# FT323H_IF.net
KiCad netlist of a schematic drawn in EAGLE
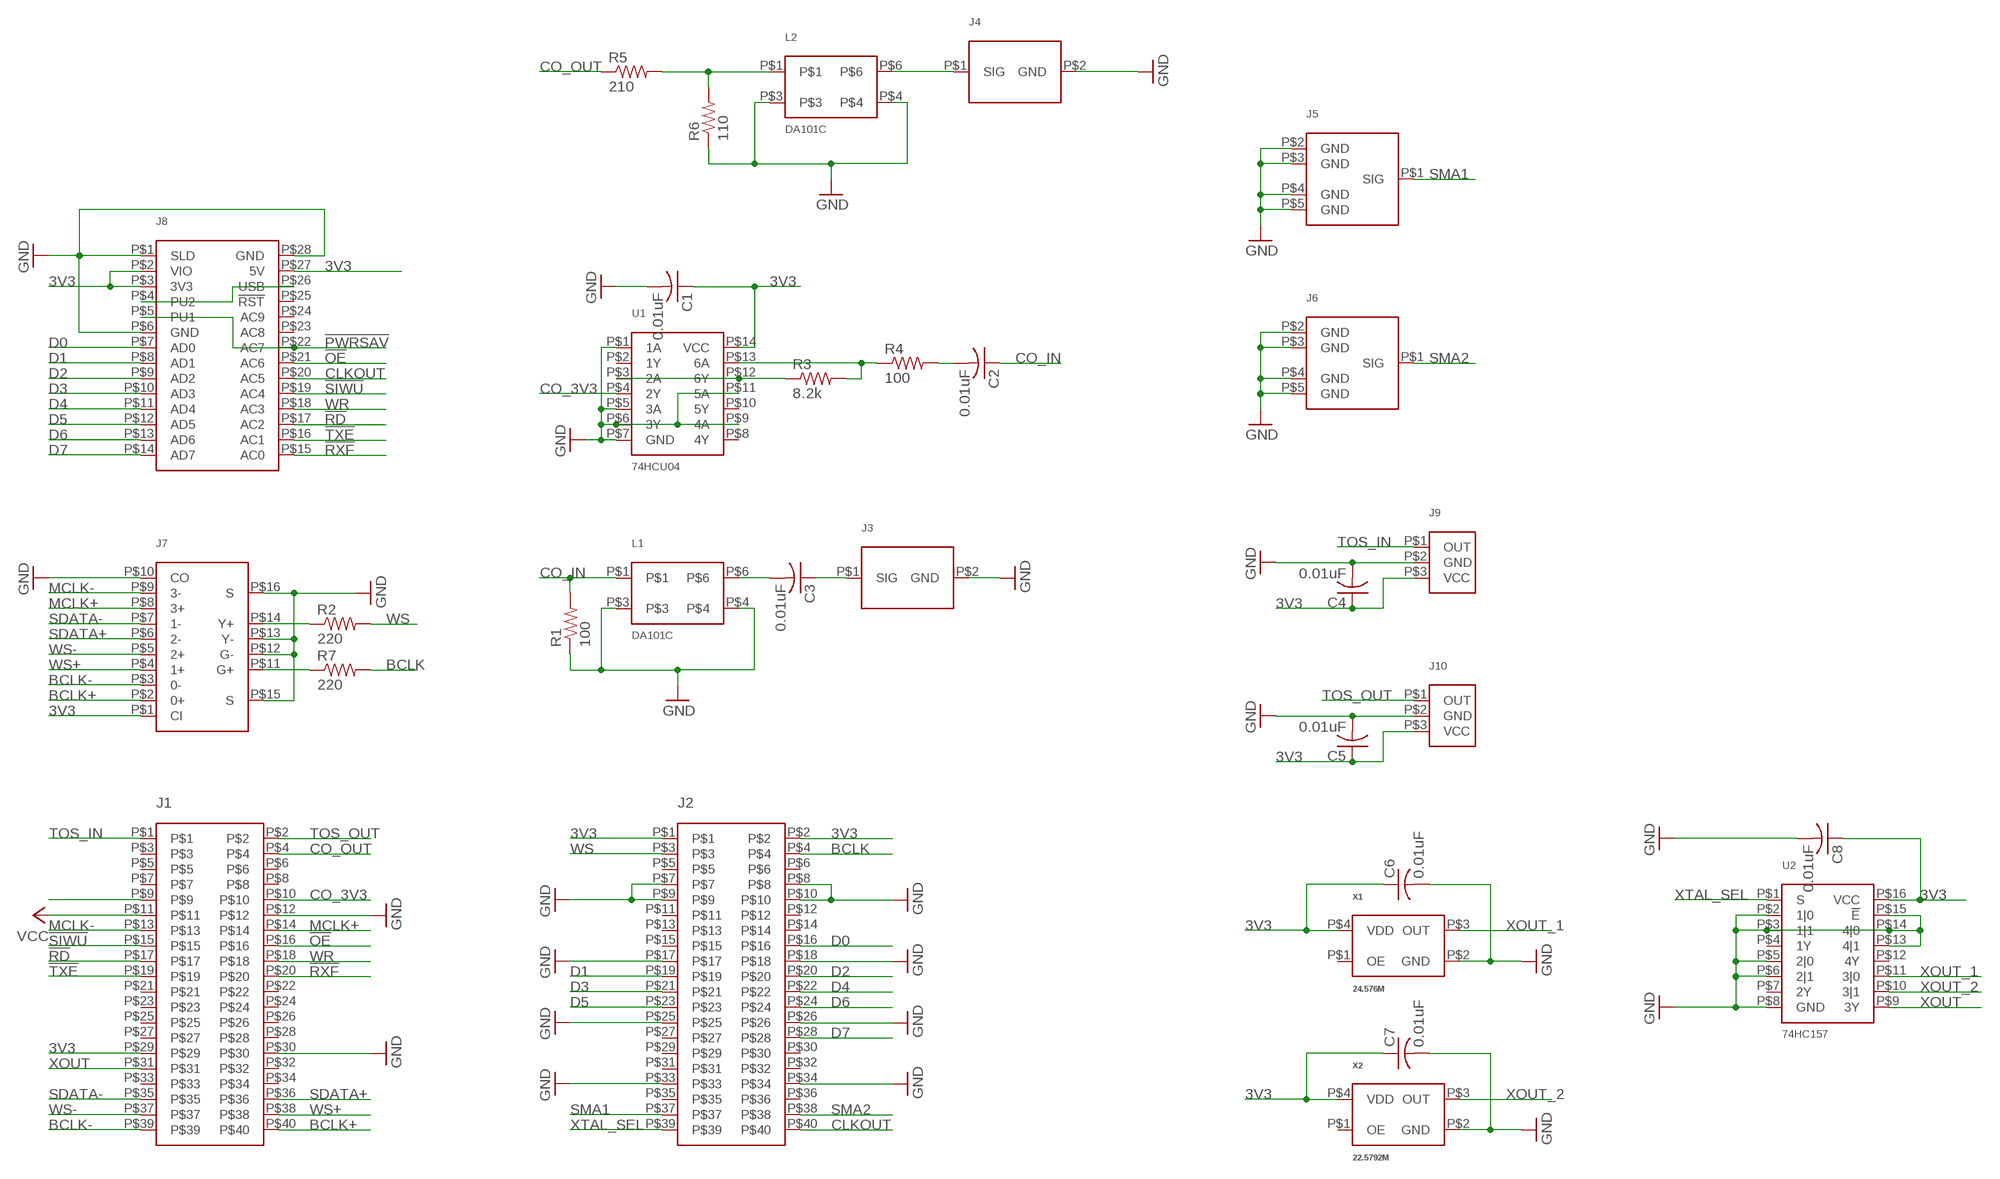
[diagram p0: schematic, sheet 1]

(export (version "E")
  (design (tool "Eeschema 10.0.6"))
  (components
    (comp (ref "C1")
      (value "0.01uF")
      (footprint "eagle-import:C0805")
      (libsource (lib "eagle-import") (part "C-USC0805"))
    )
    (comp (ref "C2")
      (value "0.01uF")
      (footprint "eagle-import:MKS2")
      (libsource (lib "eagle-import") (part "MKS2"))
    )
    (comp (ref "C3")
      (value "0.01uF")
      (footprint "eagle-import:MKS2")
      (libsource (lib "eagle-import") (part "MKS2"))
    )
    (comp (ref "C4")
      (value "0.01uF")
      (footprint "eagle-import:C0805")
      (libsource (lib "eagle-import") (part "C-USC0805"))
    )
    (comp (ref "C5")
      (value "0.01uF")
      (footprint "eagle-import:C0805")
      (libsource (lib "eagle-import") (part "C-USC0805"))
    )
    (comp (ref "C6")
      (value "0.01uF")
      (footprint "eagle-import:C0805")
      (libsource (lib "eagle-import") (part "C-USC0805"))
    )
    (comp (ref "C7")
      (value "0.01uF")
      (footprint "eagle-import:C0805")
      (libsource (lib "eagle-import") (part "C-USC0805"))
    )
    (comp (ref "C8")
      (value "0.01uF")
      (footprint "eagle-import:C0805")
      (libsource (lib "eagle-import") (part "C-USC0805"))
    )
    (comp (ref "J1")
      (value "JUMPER-2X20")
      (footprint "eagle-import:JUMPER-2X20-2.54MM")
      (libsource (lib "eagle-import") (part "JUMPER-2X20"))
    )
    (comp (ref "J2")
      (value "JUMPER-2X20")
      (footprint "eagle-import:JUMPER-2X20-2.54MM")
      (libsource (lib "eagle-import") (part "JUMPER-2X20"))
    )
    (comp (ref "J3")
      (value "RCA")
      (footprint "eagle-import:RCA")
      (libsource (lib "eagle-import") (part "RCA"))
    )
    (comp (ref "J4")
      (value "RCA")
      (footprint "eagle-import:RCA")
      (libsource (lib "eagle-import") (part "RCA"))
    )
    (comp (ref "J5")
      (value "SMA")
      (footprint "eagle-import:SMA")
      (libsource (lib "eagle-import") (part "SMA"))
    )
    (comp (ref "J6")
      (value "SMA")
      (footprint "eagle-import:SMA")
      (libsource (lib "eagle-import") (part "SMA"))
    )
    (comp (ref "J7")
      (value "HR911130C")
      (footprint "eagle-import:HR911130C")
      (libsource (lib "eagle-import") (part "HR911130C"))
    )
    (comp (ref "J8")
      (value "UM232H")
      (footprint "eagle-import:UM232H")
      (libsource (lib "eagle-import") (part "UM232H"))
    )
    (comp (ref "J9")
      (value "TORX178A")
      (footprint "eagle-import:TORX178A")
      (libsource (lib "eagle-import") (part "TORX178A"))
    )
    (comp (ref "J10")
      (value "TORX178A")
      (footprint "eagle-import:TORX178A")
      (libsource (lib "eagle-import") (part "TORX178A"))
    )
    (comp (ref "L1")
      (value "DA101C")
      (footprint "eagle-import:DA101C")
      (libsource (lib "eagle-import") (part "DA101C"))
    )
    (comp (ref "L2")
      (value "DA101C")
      (footprint "eagle-import:DA101C")
      (libsource (lib "eagle-import") (part "DA101C"))
    )
    (comp (ref "R1")
      (value "100")
      (footprint "eagle-import:RJ-24")
      (libsource (lib "eagle-import") (part "RES-RJ24"))
    )
    (comp (ref "R2")
      (value "220")
      (footprint "eagle-import:RJ-24")
      (libsource (lib "eagle-import") (part "RES-RJ24"))
    )
    (comp (ref "R3")
      (value "8.2k")
      (footprint "eagle-import:RJ-24")
      (libsource (lib "eagle-import") (part "RES-RJ24"))
    )
    (comp (ref "R4")
      (value "100")
      (footprint "eagle-import:RJ-24")
      (libsource (lib "eagle-import") (part "RES-RJ24"))
    )
    (comp (ref "R5")
      (value "210")
      (footprint "eagle-import:RJ-24")
      (libsource (lib "eagle-import") (part "RES-RJ24"))
    )
    (comp (ref "R6")
      (value "110")
      (footprint "eagle-import:RJ-24")
      (libsource (lib "eagle-import") (part "RES-RJ24"))
    )
    (comp (ref "R7")
      (value "220")
      (footprint "eagle-import:RJ-24")
      (libsource (lib "eagle-import") (part "RES-RJ24"))
    )
    (comp (ref "U1")
      (value "74HCU04")
      (footprint "eagle-import:74HCU04D")
      (libsource (lib "eagle-import") (part "74HCU04"))
    )
    (comp (ref "U2")
      (value "74HC157")
      (footprint "eagle-import:74HC157D-SO16")
      (libsource (lib "eagle-import") (part "74HC157"))
    )
    (comp (ref "X1")
      (value "24.576M")
      (footprint "eagle-import:SIT8208-0507")
      (libsource (lib "eagle-import") (part "SIT8208"))
    )
    (comp (ref "X2")
      (value "22.5792M")
      (footprint "eagle-import:SIT8208-0507")
      (libsource (lib "eagle-import") (part "SIT8208"))
    )
  )
  (nets
    (net (code "1") (name "/3V3") (class "Default")
      (node (ref "C1") (pin "1") (pinfunction "1_1") (pintype "passive"))
      (node (ref "C4") (pin "1") (pinfunction "1_1") (pintype "passive"))
      (node (ref "C5") (pin "1") (pinfunction "1_1") (pintype "passive"))
      (node (ref "C6") (pin "1") (pinfunction "1_1") (pintype "passive"))
      (node (ref "C7") (pin "1") (pinfunction "1_1") (pintype "passive"))
      (node (ref "C8") (pin "1") (pinfunction "1_1") (pintype "passive"))
      (node (ref "J1") (pin "P$29") (pinfunction "P$29_P$29") (pintype "bidirectional"))
      (node (ref "J10") (pin "P$3") (pinfunction "VCC_P$3") (pintype "bidirectional"))
      (node (ref "J2") (pin "P$1") (pinfunction "P$1_P$1") (pintype "bidirectional"))
      (node (ref "J2") (pin "P$2") (pinfunction "P$2_P$2") (pintype "bidirectional"))
      (node (ref "J7") (pin "P$1") (pinfunction "CI_P$1") (pintype "bidirectional"))
      (node (ref "J8") (pin "P$2") (pinfunction "VIO_P$2") (pintype "bidirectional"))
      (node (ref "J8") (pin "P$27") (pinfunction "5V_P$27") (pintype "bidirectional"))
      (node (ref "J8") (pin "P$3") (pinfunction "3V3_P$3") (pintype "bidirectional"))
      (node (ref "J9") (pin "P$3") (pinfunction "VCC_P$3") (pintype "bidirectional"))
      (node (ref "U1") (pin "P$14") (pinfunction "VCC_P$14") (pintype "bidirectional"))
      (node (ref "U2") (pin "P$16") (pinfunction "VCC_P$16") (pintype "bidirectional"))
      (node (ref "X1") (pin "P$4") (pinfunction "VDD_P$4") (pintype "bidirectional"))
      (node (ref "X2") (pin "P$4") (pinfunction "VDD_P$4") (pintype "bidirectional"))
    )
    (net (code "2") (name "/BCLK") (class "Default")
      (node (ref "J2") (pin "P$4") (pinfunction "P$4_P$4") (pintype "bidirectional"))
      (node (ref "R7") (pin "P$2") (pinfunction "2_P$2") (pintype "passive"))
    )
    (net (code "3") (name "/BCLK+") (class "Default")
      (node (ref "J1") (pin "P$40") (pinfunction "P$40_P$40") (pintype "bidirectional"))
      (node (ref "J7") (pin "P$2") (pinfunction "0+_P$2") (pintype "bidirectional"))
    )
    (net (code "4") (name "/BCLK-") (class "Default")
      (node (ref "J1") (pin "P$39") (pinfunction "P$39_P$39") (pintype "bidirectional"))
      (node (ref "J7") (pin "P$3") (pinfunction "0-_P$3") (pintype "bidirectional"))
    )
    (net (code "5") (name "/CLKOUT") (class "Default")
      (node (ref "J2") (pin "P$40") (pinfunction "P$40_P$40") (pintype "bidirectional"))
      (node (ref "J8") (pin "P$20") (pinfunction "AC5_P$20") (pintype "bidirectional"))
    )
    (net (code "6") (name "/CO_3V3") (class "Default")
      (node (ref "J1") (pin "P$10") (pinfunction "P$10_P$10") (pintype "bidirectional"))
      (node (ref "U1") (pin "P$4") (pinfunction "2Y_P$4") (pintype "bidirectional"))
    )
    (net (code "7") (name "/CO_IN") (class "Default")
      (node (ref "C2") (pin "P$1") (pinfunction "1_P$1") (pintype "passive"))
      (node (ref "L1") (pin "P$1") (pinfunction "P$1_P$1") (pintype "bidirectional"))
      (node (ref "R1") (pin "P$2") (pinfunction "2_P$2") (pintype "passive"))
    )
    (net (code "8") (name "/CO_OUT") (class "Default")
      (node (ref "J1") (pin "P$4") (pinfunction "P$4_P$4") (pintype "bidirectional"))
      (node (ref "R5") (pin "P$1") (pinfunction "1_P$1") (pintype "passive"))
    )
    (net (code "9") (name "/D0") (class "Default")
      (node (ref "J2") (pin "P$16") (pinfunction "P$16_P$16") (pintype "bidirectional"))
      (node (ref "J8") (pin "P$7") (pinfunction "AD0_P$7") (pintype "bidirectional"))
    )
    (net (code "10") (name "/D1") (class "Default")
      (node (ref "J2") (pin "P$19") (pinfunction "P$19_P$19") (pintype "bidirectional"))
      (node (ref "J8") (pin "P$8") (pinfunction "AD1_P$8") (pintype "bidirectional"))
    )
    (net (code "11") (name "/D2") (class "Default")
      (node (ref "J2") (pin "P$20") (pinfunction "P$20_P$20") (pintype "bidirectional"))
      (node (ref "J8") (pin "P$9") (pinfunction "AD2_P$9") (pintype "bidirectional"))
    )
    (net (code "12") (name "/D3") (class "Default")
      (node (ref "J2") (pin "P$21") (pinfunction "P$21_P$21") (pintype "bidirectional"))
      (node (ref "J8") (pin "P$10") (pinfunction "AD3_P$10") (pintype "bidirectional"))
    )
    (net (code "13") (name "/D4") (class "Default")
      (node (ref "J2") (pin "P$22") (pinfunction "P$22_P$22") (pintype "bidirectional"))
      (node (ref "J8") (pin "P$11") (pinfunction "AD4_P$11") (pintype "bidirectional"))
    )
    (net (code "14") (name "/D5") (class "Default")
      (node (ref "J2") (pin "P$23") (pinfunction "P$23_P$23") (pintype "bidirectional"))
      (node (ref "J8") (pin "P$12") (pinfunction "AD5_P$12") (pintype "bidirectional"))
    )
    (net (code "15") (name "/D6") (class "Default")
      (node (ref "J2") (pin "P$24") (pinfunction "P$24_P$24") (pintype "bidirectional"))
      (node (ref "J8") (pin "P$13") (pinfunction "AD6_P$13") (pintype "bidirectional"))
    )
    (net (code "16") (name "/D7") (class "Default")
      (node (ref "J2") (pin "P$28") (pinfunction "P$28_P$28") (pintype "bidirectional"))
      (node (ref "J8") (pin "P$14") (pinfunction "AD7_P$14") (pintype "bidirectional"))
    )
    (net (code "17") (name "/MCLK+") (class "Default")
      (node (ref "J1") (pin "P$14") (pinfunction "P$14_P$14") (pintype "bidirectional"))
      (node (ref "J7") (pin "P$8") (pinfunction "3+_P$8") (pintype "bidirectional"))
    )
    (net (code "18") (name "/MCLK-") (class "Default")
      (node (ref "J1") (pin "P$13") (pinfunction "P$13_P$13") (pintype "bidirectional"))
      (node (ref "J7") (pin "P$9") (pinfunction "3-_P$9") (pintype "bidirectional"))
    )
    (net (code "19") (name "/SDATA+") (class "Default")
      (node (ref "J1") (pin "P$36") (pinfunction "P$36_P$36") (pintype "bidirectional"))
      (node (ref "J7") (pin "P$6") (pinfunction "2-_P$6") (pintype "bidirectional"))
    )
    (net (code "20") (name "/SDATA-") (class "Default")
      (node (ref "J1") (pin "P$35") (pinfunction "P$35_P$35") (pintype "bidirectional"))
      (node (ref "J7") (pin "P$7") (pinfunction "1-_P$7") (pintype "bidirectional"))
    )
    (net (code "21") (name "/SMA1") (class "Default")
      (node (ref "J2") (pin "P$37") (pinfunction "P$37_P$37") (pintype "bidirectional"))
      (node (ref "J5") (pin "P$1") (pinfunction "SIG_P$1") (pintype "bidirectional"))
    )
    (net (code "22") (name "/SMA2") (class "Default")
      (node (ref "J2") (pin "P$38") (pinfunction "P$38_P$38") (pintype "bidirectional"))
      (node (ref "J6") (pin "P$1") (pinfunction "SIG_P$1") (pintype "bidirectional"))
    )
    (net (code "23") (name "/TOS_IN") (class "Default")
      (node (ref "J1") (pin "P$1") (pinfunction "P$1_P$1") (pintype "bidirectional"))
      (node (ref "J9") (pin "P$1") (pinfunction "OUT_P$1") (pintype "bidirectional"))
    )
    (net (code "24") (name "/TOS_OUT") (class "Default")
      (node (ref "J1") (pin "P$2") (pinfunction "P$2_P$2") (pintype "bidirectional"))
      (node (ref "J10") (pin "P$1") (pinfunction "OUT_P$1") (pintype "bidirectional"))
    )
    (net (code "25") (name "/WR") (class "Default")
      (node (ref "J1") (pin "P$18") (pinfunction "P$18_P$18") (pintype "bidirectional"))
      (node (ref "J8") (pin "P$18") (pinfunction "AC3_P$18") (pintype "bidirectional"))
    )
    (net (code "26") (name "/WS") (class "Default")
      (node (ref "J2") (pin "P$3") (pinfunction "P$3_P$3") (pintype "bidirectional"))
      (node (ref "R2") (pin "P$2") (pinfunction "2_P$2") (pintype "passive"))
    )
    (net (code "27") (name "/WS+") (class "Default")
      (node (ref "J1") (pin "P$38") (pinfunction "P$38_P$38") (pintype "bidirectional"))
      (node (ref "J7") (pin "P$4") (pinfunction "1+_P$4") (pintype "bidirectional"))
    )
    (net (code "28") (name "/WS-") (class "Default")
      (node (ref "J1") (pin "P$37") (pinfunction "P$37_P$37") (pintype "bidirectional"))
      (node (ref "J7") (pin "P$5") (pinfunction "2+_P$5") (pintype "bidirectional"))
    )
    (net (code "29") (name "/XOUT") (class "Default")
      (node (ref "J1") (pin "P$31") (pinfunction "P$31_P$31") (pintype "bidirectional"))
      (node (ref "U2") (pin "P$9") (pinfunction "3Y_P$9") (pintype "bidirectional"))
    )
    (net (code "30") (name "/XOUT_1") (class "Default")
      (node (ref "U2") (pin "P$11") (pinfunction "3|0_P$11") (pintype "bidirectional"))
      (node (ref "X1") (pin "P$3") (pinfunction "OUT_P$3") (pintype "bidirectional"))
    )
    (net (code "31") (name "/XOUT_2") (class "Default")
      (node (ref "U2") (pin "P$10") (pinfunction "3|1_P$10") (pintype "bidirectional"))
      (node (ref "X2") (pin "P$3") (pinfunction "OUT_P$3") (pintype "bidirectional"))
    )
    (net (code "32") (name "/XTAL_SEL") (class "Default")
      (node (ref "J2") (pin "P$39") (pinfunction "P$39_P$39") (pintype "bidirectional"))
      (node (ref "U2") (pin "P$1") (pinfunction "S_P$1") (pintype "bidirectional"))
    )
    (net (code "33") (name "/~{OE}") (class "Default")
      (node (ref "J1") (pin "P$16") (pinfunction "P$16_P$16") (pintype "bidirectional"))
      (node (ref "J8") (pin "P$21") (pinfunction "AC6_P$21") (pintype "bidirectional"))
    )
    (net (code "34") (name "/~{PWRSAV}") (class "Default")
      (node (ref "J8") (pin "P$22") (pinfunction "AC7_P$22") (pintype "bidirectional"))
      (node (ref "J8") (pin "P$5") (pinfunction "PU1_P$5") (pintype "bidirectional"))
    )
    (net (code "35") (name "/~{RD}") (class "Default")
      (node (ref "J1") (pin "P$17") (pinfunction "P$17_P$17") (pintype "bidirectional"))
      (node (ref "J8") (pin "P$17") (pinfunction "AC2_P$17") (pintype "bidirectional"))
    )
    (net (code "36") (name "/~{RXF}") (class "Default")
      (node (ref "J1") (pin "P$20") (pinfunction "P$20_P$20") (pintype "bidirectional"))
      (node (ref "J8") (pin "P$15") (pinfunction "AC0_P$15") (pintype "bidirectional"))
    )
    (net (code "37") (name "/~{SIWU}") (class "Default")
      (node (ref "J1") (pin "P$15") (pinfunction "P$15_P$15") (pintype "bidirectional"))
      (node (ref "J8") (pin "P$19") (pinfunction "AC4_P$19") (pintype "bidirectional"))
    )
    (net (code "38") (name "/~{TXE}") (class "Default")
      (node (ref "J1") (pin "P$19") (pinfunction "P$19_P$19") (pintype "bidirectional"))
      (node (ref "J8") (pin "P$16") (pinfunction "AC1_P$16") (pintype "bidirectional"))
    )
    (net (code "39") (name "GND") (class "Default")
      (node (ref "C1") (pin "2") (pinfunction "2_2") (pintype "passive"))
      (node (ref "C4") (pin "2") (pinfunction "2_2") (pintype "passive"))
      (node (ref "C5") (pin "2") (pinfunction "2_2") (pintype "passive"))
      (node (ref "C6") (pin "2") (pinfunction "2_2") (pintype "passive"))
      (node (ref "C7") (pin "2") (pinfunction "2_2") (pintype "passive"))
      (node (ref "C8") (pin "2") (pinfunction "2_2") (pintype "passive"))
      (node (ref "J1") (pin "P$12") (pinfunction "P$12_P$12") (pintype "bidirectional"))
      (node (ref "J1") (pin "P$30") (pinfunction "P$30_P$30") (pintype "bidirectional"))
      (node (ref "J10") (pin "P$2") (pinfunction "GND_P$2") (pintype "bidirectional"))
      (node (ref "J2") (pin "P$10") (pinfunction "P$10_P$10") (pintype "bidirectional"))
      (node (ref "J2") (pin "P$17") (pinfunction "P$17_P$17") (pintype "bidirectional"))
      (node (ref "J2") (pin "P$18") (pinfunction "P$18_P$18") (pintype "bidirectional"))
      (node (ref "J2") (pin "P$25") (pinfunction "P$25_P$25") (pintype "bidirectional"))
      (node (ref "J2") (pin "P$26") (pinfunction "P$26_P$26") (pintype "bidirectional"))
      (node (ref "J2") (pin "P$33") (pinfunction "P$33_P$33") (pintype "bidirectional"))
      (node (ref "J2") (pin "P$34") (pinfunction "P$34_P$34") (pintype "bidirectional"))
      (node (ref "J2") (pin "P$7") (pinfunction "P$7_P$7") (pintype "bidirectional"))
      (node (ref "J2") (pin "P$8") (pinfunction "P$8_P$8") (pintype "bidirectional"))
      (node (ref "J2") (pin "P$9") (pinfunction "P$9_P$9") (pintype "bidirectional"))
      (node (ref "J3") (pin "P$2") (pinfunction "GND_P$2") (pintype "bidirectional"))
      (node (ref "J4") (pin "P$2") (pinfunction "GND_P$2") (pintype "bidirectional"))
      (node (ref "J5") (pin "P$2") (pinfunction "GND_P$2") (pintype "bidirectional"))
      (node (ref "J5") (pin "P$3") (pinfunction "GND_P$3") (pintype "bidirectional"))
      (node (ref "J5") (pin "P$4") (pinfunction "GND_P$4") (pintype "bidirectional"))
      (node (ref "J5") (pin "P$5") (pinfunction "GND_P$5") (pintype "bidirectional"))
      (node (ref "J6") (pin "P$2") (pinfunction "GND_P$2") (pintype "bidirectional"))
      (node (ref "J6") (pin "P$3") (pinfunction "GND_P$3") (pintype "bidirectional"))
      (node (ref "J6") (pin "P$4") (pinfunction "GND_P$4") (pintype "bidirectional"))
      (node (ref "J6") (pin "P$5") (pinfunction "GND_P$5") (pintype "bidirectional"))
      (node (ref "J7") (pin "P$10") (pinfunction "CO_P$10") (pintype "bidirectional"))
      (node (ref "J7") (pin "P$12") (pinfunction "G-_P$12") (pintype "bidirectional"))
      (node (ref "J7") (pin "P$13") (pinfunction "Y-_P$13") (pintype "bidirectional"))
      (node (ref "J7") (pin "P$15") (pinfunction "S_P$15") (pintype "bidirectional"))
      (node (ref "J7") (pin "P$16") (pinfunction "S_P$16") (pintype "bidirectional"))
      (node (ref "J8") (pin "P$1") (pinfunction "SLD_P$1") (pintype "bidirectional"))
      (node (ref "J8") (pin "P$28") (pinfunction "GND_P$28") (pintype "bidirectional"))
      (node (ref "J8") (pin "P$6") (pinfunction "GND_P$6") (pintype "bidirectional"))
      (node (ref "J9") (pin "P$2") (pinfunction "GND_P$2") (pintype "bidirectional"))
      (node (ref "L1") (pin "P$3") (pinfunction "P$3_P$3") (pintype "bidirectional"))
      (node (ref "L1") (pin "P$4") (pinfunction "P$4_P$4") (pintype "bidirectional"))
      (node (ref "L2") (pin "P$3") (pinfunction "P$3_P$3") (pintype "bidirectional"))
      (node (ref "L2") (pin "P$4") (pinfunction "P$4_P$4") (pintype "bidirectional"))
      (node (ref "R1") (pin "P$1") (pinfunction "1_P$1") (pintype "passive"))
      (node (ref "R6") (pin "P$1") (pinfunction "1_P$1") (pintype "passive"))
      (node (ref "U1") (pin "P$1") (pinfunction "1A_P$1") (pintype "bidirectional"))
      (node (ref "U1") (pin "P$11") (pinfunction "5A_P$11") (pintype "bidirectional"))
      (node (ref "U1") (pin "P$5") (pinfunction "3A_P$5") (pintype "bidirectional"))
      (node (ref "U1") (pin "P$6") (pinfunction "3Y_P$6") (pintype "bidirectional"))
      (node (ref "U1") (pin "P$7") (pinfunction "GND_P$7") (pintype "bidirectional"))
      (node (ref "U1") (pin "P$9") (pinfunction "4A_P$9") (pintype "bidirectional"))
      (node (ref "U2") (pin "P$13") (pinfunction "4|1_P$13") (pintype "bidirectional"))
      (node (ref "U2") (pin "P$14") (pinfunction "4|0_P$14") (pintype "bidirectional"))
      (node (ref "U2") (pin "P$15") (pinfunction "~{E}_P$15") (pintype "bidirectional"))
      (node (ref "U2") (pin "P$2") (pinfunction "1|0_P$2") (pintype "bidirectional"))
      (node (ref "U2") (pin "P$3") (pinfunction "1|1_P$3") (pintype "bidirectional"))
      (node (ref "U2") (pin "P$5") (pinfunction "2|0_P$5") (pintype "bidirectional"))
      (node (ref "U2") (pin "P$6") (pinfunction "2|1_P$6") (pintype "bidirectional"))
      (node (ref "U2") (pin "P$8") (pinfunction "GND_P$8") (pintype "bidirectional"))
      (node (ref "X1") (pin "P$2") (pinfunction "GND_P$2") (pintype "bidirectional"))
      (node (ref "X2") (pin "P$2") (pinfunction "GND_P$2") (pintype "bidirectional"))
    )
    (net (code "40") (name "Net-(C2-2)") (class "Default")
      (node (ref "C2") (pin "P$2") (pinfunction "2_P$2") (pintype "passive"))
      (node (ref "R4") (pin "P$2") (pinfunction "2_P$2") (pintype "passive"))
    )
    (net (code "41") (name "Net-(C3-1)") (class "Default")
      (node (ref "C3") (pin "P$1") (pinfunction "1_P$1") (pintype "passive"))
      (node (ref "J3") (pin "P$1") (pinfunction "SIG_P$1") (pintype "bidirectional"))
    )
    (net (code "42") (name "Net-(C3-2)") (class "Default")
      (node (ref "C3") (pin "P$2") (pinfunction "2_P$2") (pintype "passive"))
      (node (ref "L1") (pin "P$6") (pinfunction "P$6_P$6") (pintype "bidirectional"))
    )
    (net (code "43") (name "Net-(J4-SIG)") (class "Default")
      (node (ref "J4") (pin "P$1") (pinfunction "SIG_P$1") (pintype "bidirectional"))
      (node (ref "L2") (pin "P$6") (pinfunction "P$6_P$6") (pintype "bidirectional"))
    )
    (net (code "44") (name "Net-(J7-G+)") (class "Default")
      (node (ref "J7") (pin "P$11") (pinfunction "G+_P$11") (pintype "bidirectional"))
      (node (ref "R7") (pin "P$1") (pinfunction "1_P$1") (pintype "passive"))
    )
    (net (code "45") (name "Net-(J7-Y+)") (class "Default")
      (node (ref "J7") (pin "P$14") (pinfunction "Y+_P$14") (pintype "bidirectional"))
      (node (ref "R2") (pin "P$1") (pinfunction "1_P$1") (pintype "passive"))
    )
    (net (code "46") (name "Net-(J8-PU2)") (class "Default")
      (node (ref "J8") (pin "P$26") (pinfunction "USB_P$26") (pintype "bidirectional"))
      (node (ref "J8") (pin "P$4") (pinfunction "PU2_P$4") (pintype "bidirectional"))
    )
    (net (code "47") (name "Net-(R3-1)") (class "Default")
      (node (ref "R3") (pin "P$1") (pinfunction "1_P$1") (pintype "passive"))
      (node (ref "U1") (pin "P$12") (pinfunction "6Y_P$12") (pintype "bidirectional"))
      (node (ref "U1") (pin "P$3") (pinfunction "2A_P$3") (pintype "bidirectional"))
    )
    (net (code "48") (name "Net-(R3-2)") (class "Default")
      (node (ref "R3") (pin "P$2") (pinfunction "2_P$2") (pintype "passive"))
      (node (ref "R4") (pin "P$1") (pinfunction "1_P$1") (pintype "passive"))
      (node (ref "U1") (pin "P$13") (pinfunction "6A_P$13") (pintype "bidirectional"))
    )
    (net (code "49") (name "Net-(R5-2)") (class "Default")
      (node (ref "L2") (pin "P$1") (pinfunction "P$1_P$1") (pintype "bidirectional"))
      (node (ref "R5") (pin "P$2") (pinfunction "2_P$2") (pintype "passive"))
      (node (ref "R6") (pin "P$2") (pinfunction "2_P$2") (pintype "passive"))
    )
    (net (code "50") (name "VCC") (class "Default")
      (node (ref "J1") (pin "P$11") (pinfunction "P$11_P$11") (pintype "bidirectional"))
    )
    (net (code "51") (name "unconnected-(J1-PadP$3)") (class "Default")
      (node (ref "J1") (pin "P$3") (pinfunction "P$3_P$3") (pintype "bidirectional"))
    )
    (net (code "52") (name "unconnected-(J1-PadP$5)") (class "Default")
      (node (ref "J1") (pin "P$5") (pinfunction "P$5_P$5") (pintype "bidirectional"))
    )
    (net (code "53") (name "unconnected-(J1-PadP$6)") (class "Default")
      (node (ref "J1") (pin "P$6") (pinfunction "P$6_P$6") (pintype "bidirectional"))
    )
    (net (code "54") (name "unconnected-(J1-PadP$7)") (class "Default")
      (node (ref "J1") (pin "P$7") (pinfunction "P$7_P$7") (pintype "bidirectional"))
    )
    (net (code "55") (name "unconnected-(J1-PadP$8)") (class "Default")
      (node (ref "J1") (pin "P$8") (pinfunction "P$8_P$8") (pintype "bidirectional"))
    )
    (net (code "56") (name "unconnected-(J1-PadP$9)") (class "Default")
      (node (ref "J1") (pin "P$9") (pinfunction "P$9_P$9") (pintype "bidirectional"))
    )
    (net (code "57") (name "unconnected-(J1-PadP$21)") (class "Default")
      (node (ref "J1") (pin "P$21") (pinfunction "P$21_P$21") (pintype "bidirectional"))
    )
    (net (code "58") (name "unconnected-(J1-PadP$22)") (class "Default")
      (node (ref "J1") (pin "P$22") (pinfunction "P$22_P$22") (pintype "bidirectional"))
    )
    (net (code "59") (name "unconnected-(J1-PadP$23)") (class "Default")
      (node (ref "J1") (pin "P$23") (pinfunction "P$23_P$23") (pintype "bidirectional"))
    )
    (net (code "60") (name "unconnected-(J1-PadP$24)") (class "Default")
      (node (ref "J1") (pin "P$24") (pinfunction "P$24_P$24") (pintype "bidirectional"))
    )
    (net (code "61") (name "unconnected-(J1-PadP$25)") (class "Default")
      (node (ref "J1") (pin "P$25") (pinfunction "P$25_P$25") (pintype "bidirectional"))
    )
    (net (code "62") (name "unconnected-(J1-PadP$26)") (class "Default")
      (node (ref "J1") (pin "P$26") (pinfunction "P$26_P$26") (pintype "bidirectional"))
    )
    (net (code "63") (name "unconnected-(J1-PadP$27)") (class "Default")
      (node (ref "J1") (pin "P$27") (pinfunction "P$27_P$27") (pintype "bidirectional"))
    )
    (net (code "64") (name "unconnected-(J1-PadP$28)") (class "Default")
      (node (ref "J1") (pin "P$28") (pinfunction "P$28_P$28") (pintype "bidirectional"))
    )
    (net (code "65") (name "unconnected-(J1-PadP$32)") (class "Default")
      (node (ref "J1") (pin "P$32") (pinfunction "P$32_P$32") (pintype "bidirectional"))
    )
    (net (code "66") (name "unconnected-(J1-PadP$33)") (class "Default")
      (node (ref "J1") (pin "P$33") (pinfunction "P$33_P$33") (pintype "bidirectional"))
    )
    (net (code "67") (name "unconnected-(J1-PadP$34)") (class "Default")
      (node (ref "J1") (pin "P$34") (pinfunction "P$34_P$34") (pintype "bidirectional"))
    )
    (net (code "68") (name "unconnected-(J2-PadP$5)") (class "Default")
      (node (ref "J2") (pin "P$5") (pinfunction "P$5_P$5") (pintype "bidirectional"))
    )
    (net (code "69") (name "unconnected-(J2-PadP$6)") (class "Default")
      (node (ref "J2") (pin "P$6") (pinfunction "P$6_P$6") (pintype "bidirectional"))
    )
    (net (code "70") (name "unconnected-(J2-PadP$11)") (class "Default")
      (node (ref "J2") (pin "P$11") (pinfunction "P$11_P$11") (pintype "bidirectional"))
    )
    (net (code "71") (name "unconnected-(J2-PadP$12)") (class "Default")
      (node (ref "J2") (pin "P$12") (pinfunction "P$12_P$12") (pintype "bidirectional"))
    )
    (net (code "72") (name "unconnected-(J2-PadP$13)") (class "Default")
      (node (ref "J2") (pin "P$13") (pinfunction "P$13_P$13") (pintype "bidirectional"))
    )
    (net (code "73") (name "unconnected-(J2-PadP$14)") (class "Default")
      (node (ref "J2") (pin "P$14") (pinfunction "P$14_P$14") (pintype "bidirectional"))
    )
    (net (code "74") (name "unconnected-(J2-PadP$15)") (class "Default")
      (node (ref "J2") (pin "P$15") (pinfunction "P$15_P$15") (pintype "bidirectional"))
    )
    (net (code "75") (name "unconnected-(J2-PadP$27)") (class "Default")
      (node (ref "J2") (pin "P$27") (pinfunction "P$27_P$27") (pintype "bidirectional"))
    )
    (net (code "76") (name "unconnected-(J2-PadP$29)") (class "Default")
      (node (ref "J2") (pin "P$29") (pinfunction "P$29_P$29") (pintype "bidirectional"))
    )
    (net (code "77") (name "unconnected-(J2-PadP$30)") (class "Default")
      (node (ref "J2") (pin "P$30") (pinfunction "P$30_P$30") (pintype "bidirectional"))
    )
    (net (code "78") (name "unconnected-(J2-PadP$31)") (class "Default")
      (node (ref "J2") (pin "P$31") (pinfunction "P$31_P$31") (pintype "bidirectional"))
    )
    (net (code "79") (name "unconnected-(J2-PadP$32)") (class "Default")
      (node (ref "J2") (pin "P$32") (pinfunction "P$32_P$32") (pintype "bidirectional"))
    )
    (net (code "80") (name "unconnected-(J2-PadP$35)") (class "Default")
      (node (ref "J2") (pin "P$35") (pinfunction "P$35_P$35") (pintype "bidirectional"))
    )
    (net (code "81") (name "unconnected-(J2-PadP$36)") (class "Default")
      (node (ref "J2") (pin "P$36") (pinfunction "P$36_P$36") (pintype "bidirectional"))
    )
    (net (code "82") (name "unconnected-(J8-AC8-PadP$23)") (class "Default")
      (node (ref "J8") (pin "P$23") (pinfunction "AC8_P$23") (pintype "bidirectional"))
    )
    (net (code "83") (name "unconnected-(J8-AC9-PadP$24)") (class "Default")
      (node (ref "J8") (pin "P$24") (pinfunction "AC9_P$24") (pintype "bidirectional"))
    )
    (net (code "84") (name "unconnected-(J8-~{RST}-PadP$25)") (class "Default")
      (node (ref "J8") (pin "P$25") (pinfunction "~{RST}_P$25") (pintype "bidirectional"))
    )
    (net (code "85") (name "unconnected-(U1-1Y-PadP$2)") (class "Default")
      (node (ref "U1") (pin "P$2") (pinfunction "1Y_P$2") (pintype "bidirectional"))
    )
    (net (code "86") (name "unconnected-(U1-4Y-PadP$8)") (class "Default")
      (node (ref "U1") (pin "P$8") (pinfunction "4Y_P$8") (pintype "bidirectional"))
    )
    (net (code "87") (name "unconnected-(U1-5Y-PadP$10)") (class "Default")
      (node (ref "U1") (pin "P$10") (pinfunction "5Y_P$10") (pintype "bidirectional"))
    )
    (net (code "88") (name "unconnected-(U2-1Y-PadP$4)") (class "Default")
      (node (ref "U2") (pin "P$4") (pinfunction "1Y_P$4") (pintype "bidirectional"))
    )
    (net (code "89") (name "unconnected-(U2-2Y-PadP$7)") (class "Default")
      (node (ref "U2") (pin "P$7") (pinfunction "2Y_P$7") (pintype "bidirectional"))
    )
    (net (code "90") (name "unconnected-(U2-4Y-PadP$12)") (class "Default")
      (node (ref "U2") (pin "P$12") (pinfunction "4Y_P$12") (pintype "bidirectional"))
    )
    (net (code "91") (name "unconnected-(X1-OE-PadP$1)") (class "Default")
      (node (ref "X1") (pin "P$1") (pinfunction "OE_P$1") (pintype "bidirectional"))
    )
    (net (code "92") (name "unconnected-(X2-OE-PadP$1)") (class "Default")
      (node (ref "X2") (pin "P$1") (pinfunction "OE_P$1") (pintype "bidirectional"))
    )
  )
)
